# STM32F7.net
KiCad netlist of a schematic drawn in Altium Designer
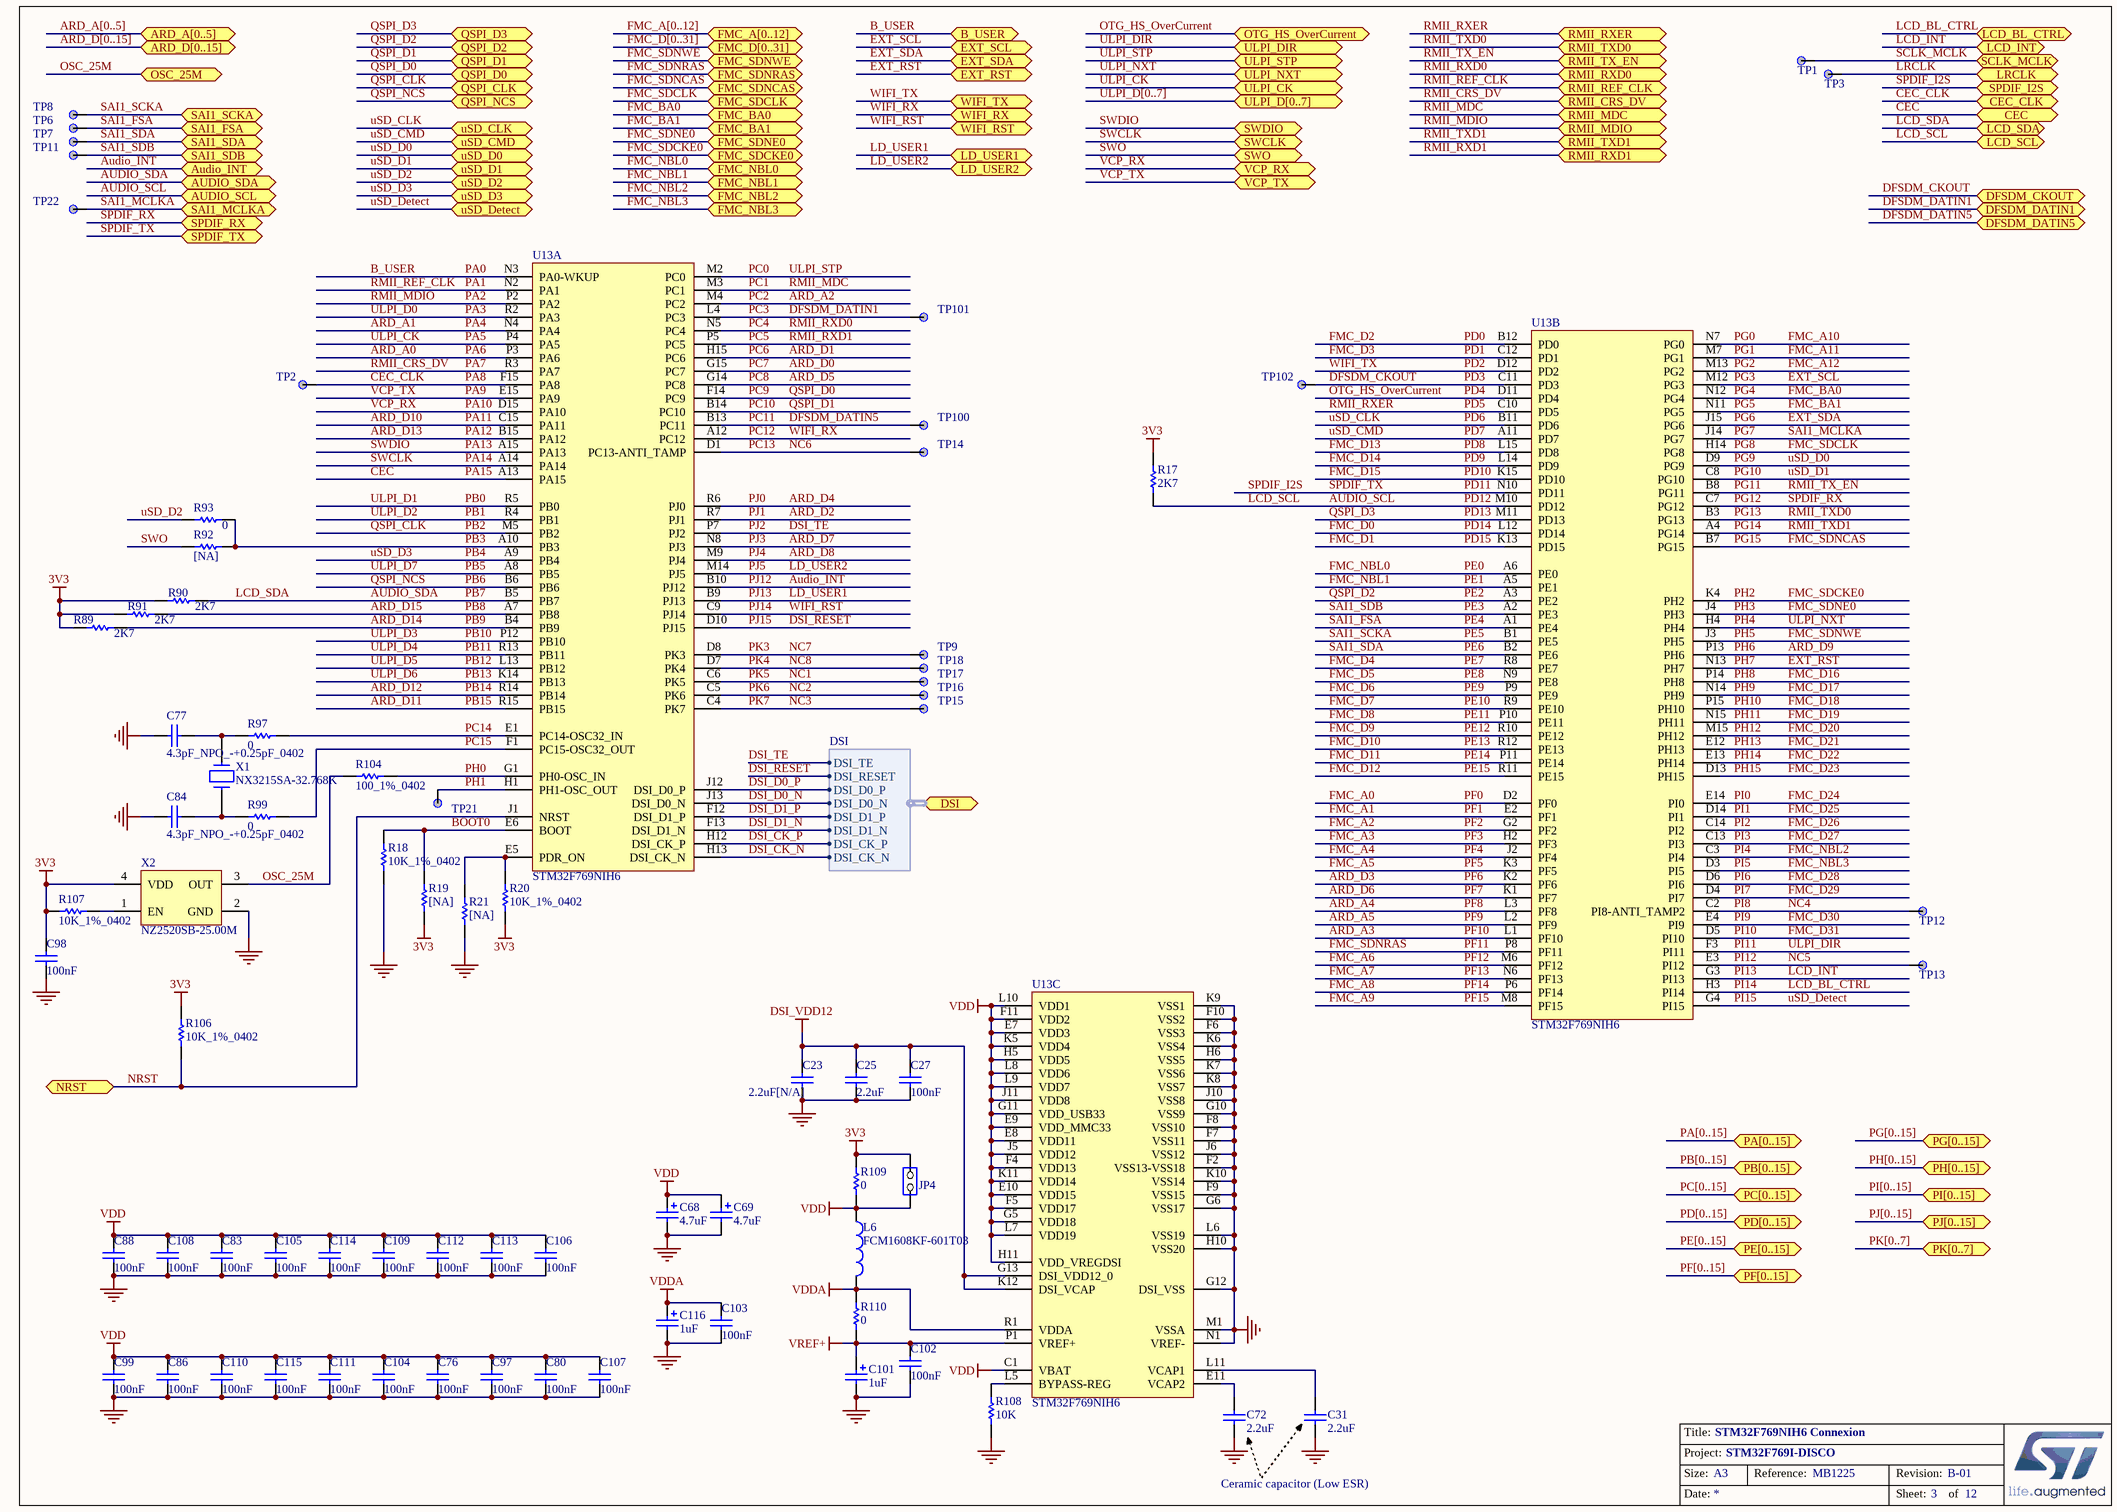
[diagram p0: STM32F7.SchDoc]

(export (version "E")
  (design (tool "Eeschema 10.0.6"))
  (components
    (comp (ref "C23")
      (value "2.2uF[N/A]")
      (footprint "1206C")
      (description "Capacitor,2.2uF,16V, X7R,10%,1206,YAGEO")
      (libsource (lib "MCD_TOOLS_CAPACITOR") (part "Cap_2.2uF_X7R_10%_1206"))
    )
    (comp (ref "C25")
      (value "2.2uF")
      (footprint "0603C")
      (description "Capacitor,2.2uF,10V, X5R,10%,0603,YAGEO")
      (libsource (lib "MCD_TOOLS_CAPACITOR") (part "Cap_2.2uF_X5R_10%_0603"))
    )
    (comp (ref "C27")
      (value "100nF")
      (footprint "0402C")
      (description "Capacitor,100nF,16V,X7R,10%,0402,YAGEO")
      (libsource (lib "MCD_TOOLS_CAPACITOR") (part "Cap_100nF_X7R_10%_0402"))
    )
    (comp (ref "C31")
      (value "2.2uF")
      (footprint "1206C")
      (description "Capacitor,2.2uF,16V, X7R,10%,1206,YAGEO")
      (libsource (lib "MCD_TOOLS") (part "Cap_2.2uF_X7R_10%_1206"))
    )
    (comp (ref "C68")
      (value "4.7uF")
      (footprint "TAN-A")
      (description "Polarized Capacitor,4.7uF,16V,10%,typeA,AVX")
      (libsource (lib "MCD_TOOLS") (part "Cap_4.7uF_POL_10%_TANA"))
    )
    (comp (ref "C69")
      (value "4.7uF")
      (footprint "TAN-A")
      (description "Polarized Capacitor,4.7uF,16V,10%,typeA,AVX")
      (libsource (lib "MCD_TOOLS") (part "Cap_4.7uF_POL_10%_TANA"))
    )
    (comp (ref "C72")
      (value "2.2uF")
      (footprint "1206C")
      (description "Capacitor,2.2uF,16V, X7R,10%,1206,YAGEO")
      (libsource (lib "MCD_TOOLS") (part "Cap_2.2uF_X7R_10%_1206"))
    )
    (comp (ref "C76")
      (value "100nF")
      (footprint "0402C")
      (description "Capacitor,100nF,16V,X7R,10%,0402,YAGEO")
      (libsource (lib "MCD_TOOLS") (part "Cap_100nF_X7R_10%_0402"))
    )
    (comp (ref "C77")
      (value "4.3pF_NPO_-+0.25pF_0402")
      (footprint "0402C")
      (description "Capacitor, 4.3pF, 16V, NPO, -+0.25pF, 0402, KEMET")
      (libsource (lib "MCD_TOOLS_CAPACITOR") (part "Cap_4.3pF_NPO_-+0.25pF_0402"))
    )
    (comp (ref "C80")
      (value "100nF")
      (footprint "0402C")
      (description "Capacitor,100nF,16V,X7R,10%,0402,YAGEO")
      (libsource (lib "MCD_TOOLS") (part "Cap_100nF_X7R_10%_0402"))
    )
    (comp (ref "C83")
      (value "100nF")
      (footprint "0402C")
      (description "Capacitor,100nF,16V,X7R,10%,0402,YAGEO")
      (libsource (lib "MCD_TOOLS") (part "Cap_100nF_X7R_10%_0402"))
    )
    (comp (ref "C84")
      (value "4.3pF_NPO_-+0.25pF_0402")
      (footprint "0402C")
      (description "Capacitor, 4.3pF, 16V, NPO, -+0.25pF, 0402, KEMET")
      (libsource (lib "MCD_TOOLS_CAPACITOR") (part "Cap_4.3pF_NPO_-+0.25pF_0402"))
    )
    (comp (ref "C86")
      (value "100nF")
      (footprint "0402C")
      (description "Capacitor,100nF,16V,X7R,10%,0402,YAGEO")
      (libsource (lib "MCD_TOOLS") (part "Cap_100nF_X7R_10%_0402"))
    )
    (comp (ref "C88")
      (value "100nF")
      (footprint "0402C")
      (description "Capacitor,100nF,16V,X7R,10%,0402,YAGEO")
      (libsource (lib "MCD_TOOLS") (part "Cap_100nF_X7R_10%_0402"))
    )
    (comp (ref "C97")
      (value "100nF")
      (footprint "0402C")
      (description "Capacitor,100nF,16V,X7R,10%,0402,YAGEO")
      (libsource (lib "MCD_TOOLS") (part "Cap_100nF_X7R_10%_0402"))
    )
    (comp (ref "C98")
      (value "100nF")
      (footprint "0402C")
      (description "Capacitor,100nF,16V,X7R,10%,0402,YAGEO")
      (libsource (lib "MCD_TOOLS") (part "Cap_100nF_X7R_10%_0402"))
    )
    (comp (ref "C99")
      (value "100nF")
      (footprint "0402C")
      (description "Capacitor,100nF,16V,X7R,10%,0402,YAGEO")
      (libsource (lib "MCD_TOOLS") (part "Cap_100nF_X7R_10%_0402"))
    )
    (comp (ref "C101")
      (value "1uF")
      (footprint "TAN-A")
      (description "Polarized Capacitor,1uF,16V,10%,typeA,AVX")
      (libsource (lib "MCD_TOOLS") (part "Cap_1uF_POL_10%_TANA"))
    )
    (comp (ref "C102")
      (value "100nF")
      (footprint "0402C")
      (description "Capacitor,100nF,16V,X7R,10%,0402,YAGEO")
      (libsource (lib "MCD_TOOLS") (part "Cap_100nF_X7R_10%_0402"))
    )
    (comp (ref "C103")
      (value "100nF")
      (footprint "0402C")
      (description "Capacitor,100nF,16V,X7R,10%,0402,YAGEO")
      (libsource (lib "MCD_TOOLS") (part "Cap_100nF_X7R_10%_0402"))
    )
    (comp (ref "C104")
      (value "100nF")
      (footprint "0402C")
      (description "Capacitor,100nF,16V,X7R,10%,0402,YAGEO")
      (libsource (lib "MCD_TOOLS") (part "Cap_100nF_X7R_10%_0402"))
    )
    (comp (ref "C105")
      (value "100nF")
      (footprint "0402C")
      (description "Capacitor,100nF,16V,X7R,10%,0402,YAGEO")
      (libsource (lib "MCD_TOOLS") (part "Cap_100nF_X7R_10%_0402"))
    )
    (comp (ref "C106")
      (value "100nF")
      (footprint "0402C")
      (description "Capacitor,100nF,16V,X7R,10%,0402,YAGEO")
      (libsource (lib "MCD_TOOLS") (part "Cap_100nF_X7R_10%_0402"))
    )
    (comp (ref "C107")
      (value "100nF")
      (footprint "0402C")
      (description "Capacitor,100nF,16V,X7R,10%,0402,YAGEO")
      (libsource (lib "MCD_TOOLS") (part "Cap_100nF_X7R_10%_0402"))
    )
    (comp (ref "C108")
      (value "100nF")
      (footprint "0402C")
      (description "Capacitor,100nF,16V,X7R,10%,0402,YAGEO")
      (libsource (lib "MCD_TOOLS") (part "Cap_100nF_X7R_10%_0402"))
    )
    (comp (ref "C109")
      (value "100nF")
      (footprint "0402C")
      (description "Capacitor,100nF,16V,X7R,10%,0402,YAGEO")
      (libsource (lib "MCD_TOOLS") (part "Cap_100nF_X7R_10%_0402"))
    )
    (comp (ref "C110")
      (value "100nF")
      (footprint "0402C")
      (description "Capacitor,100nF,16V,X7R,10%,0402,YAGEO")
      (libsource (lib "MCD_TOOLS") (part "Cap_100nF_X7R_10%_0402"))
    )
    (comp (ref "C111")
      (value "100nF")
      (footprint "0402C")
      (description "Capacitor,100nF,16V,X7R,10%,0402,YAGEO")
      (libsource (lib "MCD_TOOLS") (part "Cap_100nF_X7R_10%_0402"))
    )
    (comp (ref "C112")
      (value "100nF")
      (footprint "0402C")
      (description "Capacitor,100nF,16V,X7R,10%,0402,YAGEO")
      (libsource (lib "MCD_TOOLS") (part "Cap_100nF_X7R_10%_0402"))
    )
    (comp (ref "C113")
      (value "100nF")
      (footprint "0402C")
      (description "Capacitor,100nF,16V,X7R,10%,0402,YAGEO")
      (libsource (lib "MCD_TOOLS") (part "Cap_100nF_X7R_10%_0402"))
    )
    (comp (ref "C114")
      (value "100nF")
      (footprint "0402C")
      (description "Capacitor,100nF,16V,X7R,10%,0402,YAGEO")
      (libsource (lib "MCD_TOOLS") (part "Cap_100nF_X7R_10%_0402"))
    )
    (comp (ref "C115")
      (value "100nF")
      (footprint "0402C")
      (description "Capacitor,100nF,16V,X7R,10%,0402,YAGEO")
      (libsource (lib "MCD_TOOLS") (part "Cap_100nF_X7R_10%_0402"))
    )
    (comp (ref "C116")
      (value "1uF")
      (footprint "TAN-A")
      (description "Polarized Capacitor,1uF,16V,10%,typeA,AVX")
      (libsource (lib "MCD_TOOLS") (part "Cap_1uF_POL_10%_TANA"))
    )
    (comp (ref "JP4") (value "JP2") (footprint "SIP2") (libsource (lib "MCD_TOOLS_CONNECTOR") (part "JP2")))
    (comp (ref "L6")
      (value "FCM1608KF-601T03")
      (footprint "0603L")
      (description "Bead,600R,350mA,0603,FCM1608KF-601T03,Tai-tech")
      (libsource (lib "MCD_TOOLS") (part "BEAD_600R_350MA_0603"))
    )
    (comp (ref "R17")
      (value "2K7")
      (footprint "0402R")
      (description "Resistor,2K7,0402,1%,YAGEO")
      (libsource (lib "MCD_TOOLS") (part "Res_2K7_1%_0402"))
    )
    (comp (ref "R18")
      (value "10K_1%_0402")
      (footprint "0402R")
      (description "Resistor,10K,0402,1%,YAGEO")
      (libsource (lib "MCD_TOOLS") (part "Res_10K_1%_0402"))
    )
    (comp (ref "R19")
      (value "[NA]")
      (footprint "0402R")
      (description "Resistor,[NA],0402")
      (libsource (lib "MCD_TOOLS") (part "Res_NA_0402"))
    )
    (comp (ref "R20")
      (value "10K_1%_0402")
      (footprint "0402R")
      (description "Resistor,10K,0402,1%,YAGEO")
      (libsource (lib "MCD_TOOLS") (part "Res_10K_1%_0402"))
    )
    (comp (ref "R21")
      (value "[NA]")
      (footprint "0402R")
      (description "Resistor,[NA],0402")
      (libsource (lib "MCD_TOOLS") (part "Res_NA_0402"))
    )
    (comp (ref "R89")
      (value "2K7")
      (footprint "0402R")
      (description "Resistor,2K7,0402,1%,YAGEO")
      (libsource (lib "MCD_TOOLS") (part "Res_2K7_1%_0402"))
    )
    (comp (ref "R90")
      (value "2K7")
      (footprint "0402R")
      (description "Resistor,2K7,0402,1%,YAGEO")
      (libsource (lib "MCD_TOOLS") (part "Res_2K7_1%_0402"))
    )
    (comp (ref "R91")
      (value "2K7")
      (footprint "0402R")
      (description "Resistor,2K7,0402,1%,YAGEO")
      (libsource (lib "MCD_TOOLS") (part "Res_2K7_1%_0402"))
    )
    (comp (ref "R92")
      (value "[NA]")
      (footprint "0402R")
      (description "Resistor,[NA],0402")
      (libsource (lib "MCD_TOOLS_RESISTOR") (part "Res_NA_0402"))
    )
    (comp (ref "R93")
      (value "0")
      (footprint "0402R")
      (description "Resistor,0,0402,5%,YAGEO")
      (libsource (lib "MCD_TOOLS_RESISTOR") (part "Res_0_5%_0402"))
    )
    (comp (ref "R97")
      (value "0")
      (footprint "0402R")
      (description "Resistor,0,0402,5%,YAGEO")
      (libsource (lib "MCD_TOOLS") (part "Res_0_5%_0402"))
    )
    (comp (ref "R99")
      (value "0")
      (footprint "0402R")
      (description "Resistor,0,0402,5%,YAGEO")
      (libsource (lib "MCD_TOOLS") (part "Res_0_5%_0402"))
    )
    (comp (ref "R104")
      (value "100_1%_0402")
      (footprint "0402R")
      (description "Resistor,100,0402,1%,YAGEO")
      (libsource (lib "MCD_TOOLS") (part "Res_100_1%_0402"))
    )
    (comp (ref "R106")
      (value "10K_1%_0402")
      (footprint "0402R")
      (description "Resistor,10K,0402,1%,YAGEO")
      (libsource (lib "MCD_TOOLS") (part "Res_10K_1%_0402"))
    )
    (comp (ref "R107")
      (value "10K_1%_0402")
      (footprint "0402R")
      (description "Resistor,10K,0402,1%,YAGEO")
      (libsource (lib "MCD_TOOLS") (part "Res_10K_1%_0402"))
    )
    (comp (ref "R108")
      (value "10K")
      (footprint "0402R")
      (description "Resistor,10K,0402,1%,YAGEO")
      (libsource (lib "MCD_TOOLS") (part "Res_10K_1%_0402"))
    )
    (comp (ref "R109")
      (value "0")
      (footprint "0603R-GS")
      (description "Resistor,0,0603,5%,YAGEO")
      (libsource (lib "MCD_TOOLS") (part "Res_0_5%_0603"))
    )
    (comp (ref "R110")
      (value "0")
      (footprint "0603R-GS")
      (description "Resistor,0,0603,5%,YAGEO")
      (libsource (lib "MCD_TOOLS") (part "Res_0_5%_0603"))
    )
    (comp (ref "TP1")
      (value "TP")
      (footprint "TP_C40")
      (description "Test Point CMS")
      (libsource (lib "MCD_TOOLS_CONNECTOR") (part "TP"))
    )
    (comp (ref "TP2")
      (value "TP")
      (footprint "TP_C40")
      (description "Test Point CMS")
      (libsource (lib "MCD_TOOLS_CONNECTOR") (part "TP"))
    )
    (comp (ref "TP3")
      (value "TP")
      (footprint "TP_C40")
      (description "Test Point CMS")
      (libsource (lib "MCD_TOOLS_CONNECTOR") (part "TP"))
    )
    (comp (ref "TP6")
      (value "TP")
      (footprint "TP_C40")
      (description "Test Point CMS")
      (libsource (lib "MCD_TOOLS_CONNECTOR") (part "TP"))
    )
    (comp (ref "TP7")
      (value "TP")
      (footprint "TP_C40")
      (description "Test Point CMS")
      (libsource (lib "MCD_TOOLS_CONNECTOR") (part "TP"))
    )
    (comp (ref "TP8")
      (value "TP")
      (footprint "TP_C40")
      (description "Test Point CMS")
      (libsource (lib "MCD_TOOLS_CONNECTOR") (part "TP"))
    )
    (comp (ref "TP9")
      (value "TP")
      (footprint "TP_C40")
      (description "Test Point CMS")
      (libsource (lib "MCD_TOOLS_CONNECTOR") (part "TP"))
    )
    (comp (ref "TP11")
      (value "TP")
      (footprint "TP_C40")
      (description "Test Point CMS")
      (libsource (lib "MCD_TOOLS_CONNECTOR") (part "TP"))
    )
    (comp (ref "TP12")
      (value "TP")
      (footprint "TP_C40")
      (description "Test Point CMS")
      (libsource (lib "MCD_TOOLS_CONNECTOR") (part "TP"))
    )
    (comp (ref "TP13")
      (value "TP")
      (footprint "TP_C40")
      (description "Test Point CMS")
      (libsource (lib "MCD_TOOLS_CONNECTOR") (part "TP"))
    )
    (comp (ref "TP14")
      (value "TP")
      (footprint "TP_C40")
      (description "Test Point CMS")
      (libsource (lib "MCD_TOOLS_CONNECTOR") (part "TP"))
    )
    (comp (ref "TP15")
      (value "TP")
      (footprint "TP_C40")
      (description "Test Point CMS")
      (libsource (lib "MCD_TOOLS_CONNECTOR") (part "TP"))
    )
    (comp (ref "TP16")
      (value "TP")
      (footprint "TP_C40")
      (description "Test Point CMS")
      (libsource (lib "MCD_TOOLS_CONNECTOR") (part "TP"))
    )
    (comp (ref "TP17")
      (value "TP")
      (footprint "TP_C40")
      (description "Test Point CMS")
      (libsource (lib "MCD_TOOLS_CONNECTOR") (part "TP"))
    )
    (comp (ref "TP18")
      (value "TP")
      (footprint "TP_C40")
      (description "Test Point CMS")
      (libsource (lib "MCD_TOOLS_CONNECTOR") (part "TP"))
    )
    (comp (ref "TP21")
      (value "TP")
      (footprint "TP_C40")
      (description "Test Point CMS")
      (libsource (lib "MCD_TOOLS_CONNECTOR") (part "TP"))
    )
    (comp (ref "TP22")
      (value "TP")
      (footprint "TP_C40")
      (description "Test Point CMS")
      (libsource (lib "MCD_TOOLS_CONNECTOR") (part "TP"))
    )
    (comp (ref "TP100")
      (value "TP")
      (footprint "TP_C40")
      (description "Test Point CMS")
      (libsource (lib "MCD_TOOLS_CONNECTOR") (part "TP"))
    )
    (comp (ref "TP101")
      (value "TP")
      (footprint "TP_C40")
      (description "Test Point CMS")
      (libsource (lib "MCD_TOOLS_CONNECTOR") (part "TP"))
    )
    (comp (ref "TP102")
      (value "TP")
      (footprint "TP_C40")
      (description "Test Point CMS")
      (libsource (lib "MCD_TOOLS_CONNECTOR") (part "TP"))
    )
    (comp (ref "U13")
      (value "STM32F769NIH6")
      (footprint "BGA216_0R8_13X13")
      (description "STM32F769NIH6 (STM32F7 Big Birdie) TBGA216")
      (libsource (lib "MCD_TOOLS_MCU") (part "STM32F769NIH6U"))
    )
    (comp (ref "X1")
      (value "NX3215SA-32.768K")
      (footprint "XTAL_2SM_3R2X1R5")
      (description "Crystal 32.768kHz, 6pF, -+20PPM, NDK only for ST, Type NX3215SA,  NDK Spec EXS00A-MU00525")
      (libsource (lib "MCD_TOOLS") (part "XTAL_32K_NX3215SA"))
    )
    (comp (ref "X2")
      (value "NZ2520SB-25.00M")
      (footprint "OSC_4SM_2R5X2")
      (description "Oscillator 25.00Mhz, -+50PPM, 3.3V, Temp -55 to +125°C")
      (libsource (lib "MCD_TOOLS_MISCELLANEOUS") (part "OSC_25M_NZ2520SB"))
    )
  )
  (nets
    (net (code "11") (name "/ARD_A0") (class "Default")
      (node (ref "U13") (pin "P3") (pinfunction "PA6_P3") (pintype "passive"))
    )
    (net (code "12") (name "/ARD_A1") (class "Default")
      (node (ref "U13") (pin "N4") (pinfunction "PA4_N4") (pintype "passive"))
    )
    (net (code "13") (name "/ARD_A2") (class "Default")
      (node (ref "U13") (pin "M4") (pinfunction "PC2_M4") (pintype "passive"))
    )
    (net (code "14") (name "/ARD_A3") (class "Default")
      (node (ref "U13") (pin "L1") (pinfunction "PF10_L1") (pintype "passive"))
    )
    (net (code "15") (name "/ARD_A4") (class "Default")
      (node (ref "U13") (pin "L3") (pinfunction "PF8_L3") (pintype "passive"))
    )
    (net (code "16") (name "/ARD_A5") (class "Default")
      (node (ref "U13") (pin "L2") (pinfunction "PF9_L2") (pintype "passive"))
    )
    (net (code "18") (name "/ARD_D0") (class "Default")
      (node (ref "U13") (pin "G15") (pinfunction "PC7_G15") (pintype "passive"))
    )
    (net (code "19") (name "/ARD_D1") (class "Default")
      (node (ref "U13") (pin "H15") (pinfunction "PC6_H15") (pintype "passive"))
    )
    (net (code "20") (name "/ARD_D2") (class "Default")
      (node (ref "U13") (pin "R7") (pinfunction "PJ1_R7") (pintype "passive"))
    )
    (net (code "21") (name "/ARD_D3") (class "Default")
      (node (ref "U13") (pin "K2") (pinfunction "PF6_K2") (pintype "passive"))
    )
    (net (code "22") (name "/ARD_D4") (class "Default")
      (node (ref "U13") (pin "R6") (pinfunction "PJ0_R6") (pintype "passive"))
    )
    (net (code "23") (name "/ARD_D5") (class "Default")
      (node (ref "U13") (pin "G14") (pinfunction "PC8_G14") (pintype "passive"))
    )
    (net (code "24") (name "/ARD_D6") (class "Default")
      (node (ref "U13") (pin "K1") (pinfunction "PF7_K1") (pintype "passive"))
    )
    (net (code "25") (name "/ARD_D7") (class "Default")
      (node (ref "U13") (pin "N8") (pinfunction "PJ3_N8") (pintype "passive"))
    )
    (net (code "26") (name "/ARD_D8") (class "Default")
      (node (ref "U13") (pin "M9") (pinfunction "PJ4_M9") (pintype "passive"))
    )
    (net (code "27") (name "/ARD_D9") (class "Default")
      (node (ref "U13") (pin "P13") (pinfunction "PH6_P13") (pintype "passive"))
    )
    (net (code "28") (name "/ARD_D10") (class "Default")
      (node (ref "U13") (pin "C15") (pinfunction "PA11_C15") (pintype "passive"))
    )
    (net (code "29") (name "/ARD_D11") (class "Default")
      (node (ref "U13") (pin "R15") (pinfunction "PB15_R15") (pintype "passive"))
    )
    (net (code "30") (name "/ARD_D12") (class "Default")
      (node (ref "U13") (pin "R14") (pinfunction "PB14_R14") (pintype "passive"))
    )
    (net (code "31") (name "/ARD_D13") (class "Default")
      (node (ref "U13") (pin "B15") (pinfunction "PA12_B15") (pintype "passive"))
    )
    (net (code "32") (name "/ARD_D14") (class "Default")
      (node (ref "R89") (pin "2") (pinfunction "2_2") (pintype "passive"))
      (node (ref "U13") (pin "B4") (pinfunction "PB9_B4") (pintype "passive"))
    )
    (net (code "33") (name "/ARD_D15") (class "Default")
      (node (ref "R91") (pin "2") (pinfunction "2_2") (pintype "passive"))
      (node (ref "U13") (pin "A7") (pinfunction "PB8_A7") (pintype "passive"))
    )
    (net (code "35") (name "/BOOT0") (class "Default")
      (node (ref "R18") (pin "2") (pinfunction "2_2") (pintype "passive"))
      (node (ref "R19") (pin "2") (pinfunction "2_2") (pintype "passive"))
      (node (ref "U13") (pin "E6") (pinfunction "BOOT_E6") (pintype "passive"))
    )
    (net (code "36") (name "/DSI_CK_N") (class "Default")
      (node (ref "U13") (pin "H13") (pinfunction "DSI_CK_N_H13") (pintype "passive"))
    )
    (net (code "37") (name "/DSI_CK_P") (class "Default")
      (node (ref "U13") (pin "H12") (pinfunction "DSI_CK_P_H12") (pintype "passive"))
    )
    (net (code "38") (name "/DSI_D0_N") (class "Default")
      (node (ref "U13") (pin "J13") (pinfunction "DSI_D0_N_J13") (pintype "passive"))
    )
    (net (code "39") (name "/DSI_D0_P") (class "Default")
      (node (ref "U13") (pin "J12") (pinfunction "DSI_D0_P_J12") (pintype "passive"))
    )
    (net (code "40") (name "/DSI_D1_N") (class "Default")
      (node (ref "U13") (pin "F13") (pinfunction "DSI_D1_N_F13") (pintype "passive"))
    )
    (net (code "41") (name "/DSI_D1_P") (class "Default")
      (node (ref "U13") (pin "F12") (pinfunction "DSI_D1_P_F12") (pintype "passive"))
    )
    (net (code "42") (name "/FMC_A0") (class "Default")
      (node (ref "U13") (pin "D2") (pinfunction "PF0_D2") (pintype "passive"))
    )
    (net (code "43") (name "/FMC_A1") (class "Default")
      (node (ref "U13") (pin "E2") (pinfunction "PF1_E2") (pintype "passive"))
    )
    (net (code "44") (name "/FMC_A2") (class "Default")
      (node (ref "U13") (pin "G2") (pinfunction "PF2_G2") (pintype "passive"))
    )
    (net (code "45") (name "/FMC_A3") (class "Default")
      (node (ref "U13") (pin "H2") (pinfunction "PF3_H2") (pintype "passive"))
    )
    (net (code "46") (name "/FMC_A4") (class "Default")
      (node (ref "U13") (pin "J2") (pinfunction "PF4_J2") (pintype "passive"))
    )
    (net (code "47") (name "/FMC_A5") (class "Default")
      (node (ref "U13") (pin "K3") (pinfunction "PF5_K3") (pintype "passive"))
    )
    (net (code "48") (name "/FMC_A6") (class "Default")
      (node (ref "U13") (pin "M6") (pinfunction "PF12_M6") (pintype "passive"))
    )
    (net (code "49") (name "/FMC_A7") (class "Default")
      (node (ref "U13") (pin "N6") (pinfunction "PF13_N6") (pintype "passive"))
    )
    (net (code "50") (name "/FMC_A8") (class "Default")
      (node (ref "U13") (pin "P6") (pinfunction "PF14_P6") (pintype "passive"))
    )
    (net (code "51") (name "/FMC_A9") (class "Default")
      (node (ref "U13") (pin "M8") (pinfunction "PF15_M8") (pintype "passive"))
    )
    (net (code "52") (name "/FMC_A10") (class "Default")
      (node (ref "U13") (pin "N7") (pinfunction "PG0_N7") (pintype "passive"))
    )
    (net (code "53") (name "/FMC_A11") (class "Default")
      (node (ref "U13") (pin "M7") (pinfunction "PG1_M7") (pintype "passive"))
    )
    (net (code "54") (name "/FMC_A12") (class "Default")
      (node (ref "U13") (pin "M13") (pinfunction "PG2_M13") (pintype "passive"))
    )
    (net (code "56") (name "/FMC_D0") (class "Default")
      (node (ref "U13") (pin "L12") (pinfunction "PD14_L12") (pintype "passive"))
    )
    (net (code "57") (name "/FMC_D1") (class "Default")
      (node (ref "U13") (pin "K13") (pinfunction "PD15_K13") (pintype "passive"))
    )
    (net (code "58") (name "/FMC_D2") (class "Default")
      (node (ref "U13") (pin "B12") (pinfunction "PD0_B12") (pintype "passive"))
    )
    (net (code "59") (name "/FMC_D3") (class "Default")
      (node (ref "U13") (pin "C12") (pinfunction "PD1_C12") (pintype "passive"))
    )
    (net (code "60") (name "/FMC_D4") (class "Default")
      (node (ref "U13") (pin "R8") (pinfunction "PE7_R8") (pintype "passive"))
    )
    (net (code "61") (name "/FMC_D5") (class "Default")
      (node (ref "U13") (pin "N9") (pinfunction "PE8_N9") (pintype "passive"))
    )
    (net (code "62") (name "/FMC_D6") (class "Default")
      (node (ref "U13") (pin "P9") (pinfunction "PE9_P9") (pintype "passive"))
    )
    (net (code "63") (name "/FMC_D7") (class "Default")
      (node (ref "U13") (pin "R9") (pinfunction "PE10_R9") (pintype "passive"))
    )
    (net (code "64") (name "/FMC_D8") (class "Default")
      (node (ref "U13") (pin "P10") (pinfunction "PE11_P10") (pintype "passive"))
    )
    (net (code "65") (name "/FMC_D9") (class "Default")
      (node (ref "U13") (pin "R10") (pinfunction "PE12_R10") (pintype "passive"))
    )
    (net (code "66") (name "/FMC_D10") (class "Default")
      (node (ref "U13") (pin "R12") (pinfunction "PE13_R12") (pintype "passive"))
    )
    (net (code "67") (name "/FMC_D11") (class "Default")
      (node (ref "U13") (pin "P11") (pinfunction "PE14_P11") (pintype "passive"))
    )
    (net (code "68") (name "/FMC_D12") (class "Default")
      (node (ref "U13") (pin "R11") (pinfunction "PE15_R11") (pintype "passive"))
    )
    (net (code "69") (name "/FMC_D13") (class "Default")
      (node (ref "U13") (pin "L15") (pinfunction "PD8_L15") (pintype "passive"))
    )
    (net (code "70") (name "/FMC_D14") (class "Default")
      (node (ref "U13") (pin "L14") (pinfunction "PD9_L14") (pintype "passive"))
    )
    (net (code "71") (name "/FMC_D15") (class "Default")
      (node (ref "U13") (pin "K15") (pinfunction "PD10_K15") (pintype "passive"))
    )
    (net (code "72") (name "/FMC_D16") (class "Default")
      (node (ref "U13") (pin "P14") (pinfunction "PH8_P14") (pintype "passive"))
    )
    (net (code "73") (name "/FMC_D17") (class "Default")
      (node (ref "U13") (pin "N14") (pinfunction "PH9_N14") (pintype "passive"))
    )
    (net (code "74") (name "/FMC_D18") (class "Default")
      (node (ref "U13") (pin "P15") (pinfunction "PH10_P15") (pintype "passive"))
    )
    (net (code "75") (name "/FMC_D19") (class "Default")
      (node (ref "U13") (pin "N15") (pinfunction "PH11_N15") (pintype "passive"))
    )
    (net (code "76") (name "/FMC_D20") (class "Default")
      (node (ref "U13") (pin "M15") (pinfunction "PH12_M15") (pintype "passive"))
    )
    (net (code "77") (name "/FMC_D21") (class "Default")
      (node (ref "U13") (pin "E12") (pinfunction "PH13_E12") (pintype "passive"))
    )
    (net (code "78") (name "/FMC_D22") (class "Default")
      (node (ref "U13") (pin "E13") (pinfunction "PH14_E13") (pintype "passive"))
    )
    (net (code "79") (name "/FMC_D23") (class "Default")
      (node (ref "U13") (pin "D13") (pinfunction "PH15_D13") (pintype "passive"))
    )
    (net (code "80") (name "/FMC_D24") (class "Default")
      (node (ref "U13") (pin "E14") (pinfunction "PI0_E14") (pintype "passive"))
    )
    (net (code "81") (name "/FMC_D25") (class "Default")
      (node (ref "U13") (pin "D14") (pinfunction "PI1_D14") (pintype "passive"))
    )
    (net (code "82") (name "/FMC_D26") (class "Default")
      (node (ref "U13") (pin "C14") (pinfunction "PI2_C14") (pintype "passive"))
    )
    (net (code "83") (name "/FMC_D27") (class "Default")
      (node (ref "U13") (pin "C13") (pinfunction "PI3_C13") (pintype "passive"))
    )
    (net (code "84") (name "/FMC_D28") (class "Default")
      (node (ref "U13") (pin "D6") (pinfunction "PI6_D6") (pintype "passive"))
    )
    (net (code "85") (name "/FMC_D29") (class "Default")
      (node (ref "U13") (pin "D4") (pinfunction "PI7_D4") (pintype "passive"))
    )
    (net (code "86") (name "/FMC_D30") (class "Default")
      (node (ref "U13") (pin "E4") (pinfunction "PI9_E4") (pintype "passive"))
    )
    (net (code "87") (name "/FMC_D31") (class "Default")
      (node (ref "U13") (pin "D5") (pinfunction "PI10_D5") (pintype "passive"))
    )
    (net (code "89") (name "/LRCLK") (class "Default")
      (node (ref "TP3") (pin "1") (pinfunction "1_1") (pintype "passive"))
    )
    (net (code "90") (name "/NRST") (class "Default")
      (node (ref "R106") (pin "1") (pinfunction "1_1") (pintype "passive"))
      (node (ref "U13") (pin "J1") (pinfunction "NRST_J1") (pintype "passive"))
    )
    (net (code "91") (name "/OSC_25M") (class "Default")
      (node (ref "R104") (pin "1") (pinfunction "1_1") (pintype "passive"))
      (node (ref "X2") (pin "3") (pinfunction "OUT_3") (pintype "passive"))
    )
    (net (code "92") (name "/PA0") (class "Default")
      (node (ref "U13") (pin "N3") (pinfunction "PA0-WKUP_N3") (pintype "passive"))
    )
    (net (code "93") (name "/PA1") (class "Default")
      (node (ref "U13") (pin "N2") (pinfunction "PA1_N2") (pintype "passive"))
    )
    (net (code "94") (name "/PA2") (class "Default")
      (node (ref "U13") (pin "P2") (pinfunction "PA2_P2") (pintype "passive"))
    )
    (net (code "95") (name "/PA5") (class "Default")
      (node (ref "U13") (pin "P4") (pinfunction "PA5_P4") (pintype "passive"))
    )
    (net (code "96") (name "/PA7") (class "Default")
      (node (ref "U13") (pin "R3") (pinfunction "PA7_R3") (pintype "passive"))
    )
    (net (code "97") (name "/PA8") (class "Default")
      (node (ref "TP2") (pin "1") (pinfunction "1_1") (pintype "passive"))
      (node (ref "U13") (pin "F15") (pinfunction "PA8_F15") (pintype "passive"))
    )
    (net (code "98") (name "/PA9") (class "Default")
      (node (ref "U13") (pin "E15") (pinfunction "PA9_E15") (pintype "passive"))
    )
    (net (code "99") (name "/PA10") (class "Default")
      (node (ref "U13") (pin "D15") (pinfunction "PA10_D15") (pintype "passive"))
    )
    (net (code "100") (name "/PA13") (class "Default")
      (node (ref "U13") (pin "A15") (pinfunction "PA13_A15") (pintype "passive"))
    )
    (net (code "101") (name "/PA14") (class "Default")
      (node (ref "U13") (pin "A14") (pinfunction "PA14_A14") (pintype "passive"))
    )
    (net (code "102") (name "/PA15") (class "Default")
      (node (ref "U13") (pin "A13") (pinfunction "PA15_A13") (pintype "passive"))
    )
    (net (code "104") (name "/PB2") (class "Default")
      (node (ref "U13") (pin "M5") (pinfunction "PB2_M5") (pintype "passive"))
    )
    (net (code "105") (name "/PB3") (class "Default")
      (node (ref "R92") (pin "2") (pinfunction "2_2") (pintype "passive"))
      (node (ref "R93") (pin "2") (pinfunction "2_2") (pintype "passive"))
      (node (ref "U13") (pin "A10") (pinfunction "PB3_A10") (pintype "passive"))
    )
    (net (code "106") (name "/PB4") (class "Default")
      (node (ref "U13") (pin "A9") (pinfunction "PB4_A9") (pintype "passive"))
    )
    (net (code "107") (name "/PB6") (class "Default")
      (node (ref "U13") (pin "B6") (pinfunction "PB6_B6") (pintype "passive"))
    )
    (net (code "108") (name "/PB7") (class "Default")
      (node (ref "R90") (pin "2") (pinfunction "2_2") (pintype "passive"))
      (node (ref "U13") (pin "B5") (pinfunction "PB7_B5") (pintype "passive"))
    )
    (net (code "110") (name "/PC0") (class "Default")
      (node (ref "U13") (pin "M2") (pinfunction "PC0_M2") (pintype "passive"))
    )
    (net (code "111") (name "/PC1") (class "Default")
      (node (ref "U13") (pin "M3") (pinfunction "PC1_M3") (pintype "passive"))
    )
    (net (code "112") (name "/PC3") (class "Default")
      (node (ref "TP101") (pin "1") (pinfunction "1_1") (pintype "passive"))
      (node (ref "U13") (pin "L4") (pinfunction "PC3_L4") (pintype "passive"))
    )
    (net (code "113") (name "/PC4") (class "Default")
      (node (ref "U13") (pin "N5") (pinfunction "PC4_N5") (pintype "passive"))
    )
    (net (code "114") (name "/PC5") (class "Default")
      (node (ref "U13") (pin "P5") (pinfunction "PC5_P5") (pintype "passive"))
    )
    (net (code "115") (name "/PC9") (class "Default")
      (node (ref "U13") (pin "F14") (pinfunction "PC9_F14") (pintype "passive"))
    )
    (net (code "116") (name "/PC10") (class "Default")
      (node (ref "U13") (pin "B14") (pinfunction "PC10_B14") (pintype "passive"))
    )
    (net (code "117") (name "/PC11") (class "Default")
      (node (ref "TP100") (pin "1") (pinfunction "1_1") (pintype "passive"))
      (node (ref "U13") (pin "B13") (pinfunction "PC11_B13") (pintype "passive"))
    )
    (net (code "118") (name "/PC12") (class "Default")
      (node (ref "U13") (pin "A12") (pinfunction "PC12_A12") (pintype "passive"))
    )
    (net (code "119") (name "/PC13") (class "Default")
      (node (ref "TP14") (pin "1") (pinfunction "1_1") (pintype "passive"))
      (node (ref "U13") (pin "D1") (pinfunction "PC13-ANTI_TAMP_D1") (pintype "passive"))
    )
    (net (code "120") (name "/PC14") (class "Default")
      (node (ref "R97") (pin "2") (pinfunction "2_2") (pintype "passive"))
      (node (ref "U13") (pin "E1") (pinfunction "PC14-OSC32_IN_E1") (pintype "passive"))
    )
    (net (code "121") (name "/PC15") (class "Default")
      (node (ref "R99") (pin "2") (pinfunction "2_2") (pintype "passive"))
      (node (ref "U13") (pin "F1") (pinfunction "PC15-OSC32_OUT_F1") (pintype "passive"))
    )
    (net (code "123") (name "/PD2") (class "Default")
      (node (ref "U13") (pin "D12") (pinfunction "PD2_D12") (pintype "passive"))
    )
    (net (code "124") (name "/PD3") (class "Default")
      (node (ref "TP102") (pin "1") (pinfunction "1_1") (pintype "passive"))
      (node (ref "U13") (pin "C11") (pinfunction "PD3_C11") (pintype "passive"))
    )
    (net (code "125") (name "/PD4") (class "Default")
      (node (ref "U13") (pin "D11") (pinfunction "PD4_D11") (pintype "passive"))
    )
    (net (code "126") (name "/PD5") (class "Default")
      (node (ref "U13") (pin "C10") (pinfunction "PD5_C10") (pintype "passive"))
    )
    (net (code "127") (name "/PD6") (class "Default")
      (node (ref "U13") (pin "B11") (pinfunction "PD6_B11") (pintype "passive"))
    )
    (net (code "128") (name "/PD7") (class "Default")
      (node (ref "U13") (pin "A11") (pinfunction "PD7_A11") (pintype "passive"))
    )
    (net (code "129") (name "/PD11") (class "Default")
      (node (ref "U13") (pin "N10") (pinfunction "PD11_N10") (pintype "passive"))
    )
    (net (code "130") (name "/PD12") (class "Default")
      (node (ref "R17") (pin "1") (pinfunction "1_1") (pintype "passive"))
      (node (ref "U13") (pin "M10") (pinfunction "PD12_M10") (pintype "passive"))
    )
    (net (code "131") (name "/PD13") (class "Default")
      (node (ref "U13") (pin "M11") (pinfunction "PD13_M11") (pintype "passive"))
    )
    (net (code "133") (name "/PE0") (class "Default")
      (node (ref "U13") (pin "A6") (pinfunction "PE0_A6") (pintype "passive"))
    )
    (net (code "134") (name "/PE1") (class "Default")
      (node (ref "U13") (pin "A5") (pinfunction "PE1_A5") (pintype "passive"))
    )
    (net (code "135") (name "/PE2") (class "Default")
      (node (ref "U13") (pin "A3") (pinfunction "PE2_A3") (pintype "passive"))
    )
    (net (code "136") (name "/PE3") (class "Default")
      (node (ref "TP11") (pin "1") (pinfunction "1_1") (pintype "passive"))
      (node (ref "U13") (pin "A2") (pinfunction "PE3_A2") (pintype "passive"))
    )
    (net (code "137") (name "/PE4") (class "Default")
      (node (ref "TP6") (pin "1") (pinfunction "1_1") (pintype "passive"))
      (node (ref "U13") (pin "A1") (pinfunction "PE4_A1") (pintype "passive"))
    )
    (net (code "138") (name "/PE5") (class "Default")
      (node (ref "TP8") (pin "1") (pinfunction "1_1") (pintype "passive"))
      (node (ref "U13") (pin "B1") (pinfunction "PE5_B1") (pintype "passive"))
    )
    (net (code "139") (name "/PE6") (class "Default")
      (node (ref "TP7") (pin "1") (pinfunction "1_1") (pintype "passive"))
      (node (ref "U13") (pin "B2") (pinfunction "PE6_B2") (pintype "passive"))
    )
    (net (code "141") (name "/PF11") (class "Default")
      (node (ref "U13") (pin "P8") (pinfunction "PF11_P8") (pintype "passive"))
    )
    (net (code "143") (name "/PG3") (class "Default")
      (node (ref "U13") (pin "M12") (pinfunction "PG3_M12") (pintype "passive"))
    )
    (net (code "144") (name "/PG4") (class "Default")
      (node (ref "U13") (pin "N12") (pinfunction "PG4_N12") (pintype "passive"))
    )
    (net (code "145") (name "/PG5") (class "Default")
      (node (ref "U13") (pin "N11") (pinfunction "PG5_N11") (pintype "passive"))
    )
    (net (code "146") (name "/PG6") (class "Default")
      (node (ref "U13") (pin "J15") (pinfunction "PG6_J15") (pintype "passive"))
    )
    (net (code "147") (name "/PG7") (class "Default")
      (node (ref "TP22") (pin "1") (pinfunction "1_1") (pintype "passive"))
      (node (ref "U13") (pin "J14") (pinfunction "PG7_J14") (pintype "passive"))
    )
    (net (code "148") (name "/PG8") (class "Default")
      (node (ref "U13") (pin "H14") (pinfunction "PG8_H14") (pintype "passive"))
    )
    (net (code "149") (name "/PG9") (class "Default")
      (node (ref "U13") (pin "D9") (pinfunction "PG9_D9") (pintype "passive"))
    )
    (net (code "150") (name "/PG10") (class "Default")
      (node (ref "U13") (pin "C8") (pinfunction "PG10_C8") (pintype "passive"))
    )
    (net (code "151") (name "/PG11") (class "Default")
      (node (ref "U13") (pin "B8") (pinfunction "PG11_B8") (pintype "passive"))
    )
    (net (code "152") (name "/PG12") (class "Default")
      (node (ref "U13") (pin "C7") (pinfunction "PG12_C7") (pintype "passive"))
    )
    (net (code "153") (name "/PG13") (class "Default")
      (node (ref "U13") (pin "B3") (pinfunction "PG13_B3") (pintype "passive"))
    )
    (net (code "154") (name "/PG14") (class "Default")
      (node (ref "U13") (pin "A4") (pinfunction "PG14_A4") (pintype "passive"))
    )
    (net (code "155") (name "/PG15") (class "Default")
      (node (ref "U13") (pin "B7") (pinfunction "PG15_B7") (pintype "passive"))
    )
    (net (code "157") (name "/PH0") (class "Default")
      (node (ref "R104") (pin "2") (pinfunction "2_2") (pintype "passive"))
      (node (ref "U13") (pin "G1") (pinfunction "PH0-OSC_IN_G1") (pintype "passive"))
    )
    (net (code "158") (name "/PH1") (class "Default")
      (node (ref "TP21") (pin "1") (pinfunction "1_1") (pintype "passive"))
      (node (ref "U13") (pin "H1") (pinfunction "PH1-OSC_OUT_H1") (pintype "passive"))
    )
    (net (code "159") (name "/PH2") (class "Default")
      (node (ref "U13") (pin "K4") (pinfunction "PH2_K4") (pintype "passive"))
    )
    (net (code "160") (name "/PH3") (class "Default")
      (node (ref "U13") (pin "J4") (pinfunction "PH3_J4") (pintype "passive"))
    )
    (net (code "161") (name "/PH4") (class "Default")
      (node (ref "U13") (pin "H4") (pinfunction "PH4_H4") (pintype "passive"))
    )
    (net (code "162") (name "/PH5") (class "Default")
      (node (ref "U13") (pin "J3") (pinfunction "PH5_J3") (pintype "passive"))
    )
    (net (code "163") (name "/PH7") (class "Default")
      (node (ref "U13") (pin "N13") (pinfunction "PH7_N13") (pintype "passive"))
    )
    (net (code "165") (name "/PI4") (class "Default")
      (node (ref "U13") (pin "C3") (pinfunction "PI4_C3") (pintype "passive"))
    )
    (net (code "166") (name "/PI5") (class "Default")
      (node (ref "U13") (pin "D3") (pinfunction "PI5_D3") (pintype "passive"))
    )
    (net (code "167") (name "/PI8") (class "Default")
      (node (ref "TP12") (pin "1") (pinfunction "1_1") (pintype "passive"))
      (node (ref "U13") (pin "C2") (pinfunction "PI8-ANTI_TAMP2_C2") (pintype "passive"))
    )
    (net (code "168") (name "/PI11") (class "Default")
      (node (ref "U13") (pin "F3") (pinfunction "PI11_F3") (pintype "passive"))
    )
    (net (code "169") (name "/PI12") (class "Default")
      (node (ref "TP13") (pin "1") (pinfunction "1_1") (pintype "passive"))
      (node (ref "U13") (pin "E3") (pinfunction "PI12_E3") (pintype "passive"))
    )
    (net (code "170") (name "/PI13") (class "Default")
      (node (ref "U13") (pin "G3") (pinfunction "PI13_G3") (pintype "passive"))
    )
    (net (code "171") (name "/PI14") (class "Default")
      (node (ref "U13") (pin "H3") (pinfunction "PI14_H3") (pintype "passive"))
    )
    (net (code "172") (name "/PI15") (class "Default")
      (node (ref "U13") (pin "G4") (pinfunction "PI15_G4") (pintype "passive"))
    )
    (net (code "174") (name "/PJ2") (class "Default")
      (node (ref "U13") (pin "P7") (pinfunction "PJ2_P7") (pintype "passive"))
    )
    (net (code "175") (name "/PJ5") (class "Default")
      (node (ref "U13") (pin "M14") (pinfunction "PJ5_M14") (pintype "passive"))
    )
    (net (code "176") (name "/PJ12") (class "Default")
      (node (ref "U13") (pin "B10") (pinfunction "PJ12_B10") (pintype "passive"))
    )
    (net (code "177") (name "/PJ13") (class "Default")
      (node (ref "U13") (pin "B9") (pinfunction "PJ13_B9") (pintype "passive"))
    )
    (net (code "178") (name "/PJ14") (class "Default")
      (node (ref "U13") (pin "C9") (pinfunction "PJ14_C9") (pintype "passive"))
    )
    (net (code "179") (name "/PJ15") (class "Default")
      (node (ref "U13") (pin "D10") (pinfunction "PJ15_D10") (pintype "passive"))
    )
    (net (code "181") (name "/PK3") (class "Default")
      (node (ref "TP9") (pin "1") (pinfunction "1_1") (pintype "passive"))
      (node (ref "U13") (pin "D8") (pinfunction "PK3_D8") (pintype "passive"))
    )
    (net (code "182") (name "/PK4") (class "Default")
      (node (ref "TP18") (pin "1") (pinfunction "1_1") (pintype "passive"))
      (node (ref "U13") (pin "D7") (pinfunction "PK4_D7") (pintype "passive"))
    )
    (net (code "183") (name "/PK5") (class "Default")
      (node (ref "TP17") (pin "1") (pinfunction "1_1") (pintype "passive"))
      (node (ref "U13") (pin "C6") (pinfunction "PK5_C6") (pintype "passive"))
    )
    (net (code "184") (name "/PK6") (class "Default")
      (node (ref "TP16") (pin "1") (pinfunction "1_1") (pintype "passive"))
      (node (ref "U13") (pin "C5") (pinfunction "PK6_C5") (pintype "passive"))
    )
    (net (code "185") (name "/PK7") (class "Default")
      (node (ref "TP15") (pin "1") (pinfunction "1_1") (pintype "passive"))
      (node (ref "U13") (pin "C4") (pinfunction "PK7_C4") (pintype "passive"))
    )
    (net (code "187") (name "/SCLK_MCLK") (class "Default")
      (node (ref "TP1") (pin "1") (pinfunction "1_1") (pintype "passive"))
    )
    (net (code "188") (name "/SWO") (class "Default")
      (node (ref "R92") (pin "1") (pinfunction "1_1") (pintype "passive"))
    )
    (net (code "189") (name "/ULPI_D0") (class "Default")
      (node (ref "U13") (pin "R2") (pinfunction "PA3_R2") (pintype "passive"))
    )
    (net (code "190") (name "/ULPI_D1") (class "Default")
      (node (ref "U13") (pin "R5") (pinfunction "PB0_R5") (pintype "passive"))
    )
    (net (code "191") (name "/ULPI_D2") (class "Default")
      (node (ref "U13") (pin "R4") (pinfunction "PB1_R4") (pintype "passive"))
    )
    (net (code "192") (name "/ULPI_D3") (class "Default")
      (node (ref "U13") (pin "P12") (pinfunction "PB10_P12") (pintype "passive"))
    )
    (net (code "193") (name "/ULPI_D4") (class "Default")
      (node (ref "U13") (pin "R13") (pinfunction "PB11_R13") (pintype "passive"))
    )
    (net (code "194") (name "/ULPI_D5") (class "Default")
      (node (ref "U13") (pin "L13") (pinfunction "PB12_L13") (pintype "passive"))
    )
    (net (code "195") (name "/ULPI_D6") (class "Default")
      (node (ref "U13") (pin "K14") (pinfunction "PB13_K14") (pintype "passive"))
    )
    (net (code "196") (name "/ULPI_D7") (class "Default")
      (node (ref "U13") (pin "A8") (pinfunction "PB5_A8") (pintype "passive"))
    )
    (net (code "198") (name "/uSD_D2") (class "Default")
      (node (ref "R93") (pin "1") (pinfunction "1_1") (pintype "passive"))
    )
    (net (code "200") (name "3V3") (class "Default")
      (node (ref "C98") (pin "2") (pinfunction "2_2") (pintype "passive"))
      (node (ref "JP4") (pin "2") (pinfunction "NO_2") (pintype "passive"))
      (node (ref "R106") (pin "2") (pinfunction "2_2") (pintype "passive"))
      (node (ref "R107") (pin "1") (pinfunction "1_1") (pintype "passive"))
      (node (ref "R109") (pin "2") (pinfunction "2_2") (pintype "passive"))
      (node (ref "R17") (pin "2") (pinfunction "2_2") (pintype "passive"))
      (node (ref "R19") (pin "1") (pinfunction "1_1") (pintype "passive"))
      (node (ref "R20") (pin "1") (pinfunction "1_1") (pintype "passive"))
      (node (ref "R89") (pin "1") (pinfunction "1_1") (pintype "passive"))
      (node (ref "R90") (pin "1") (pinfunction "1_1") (pintype "passive"))
      (node (ref "R91") (pin "1") (pinfunction "1_1") (pintype "passive"))
      (node (ref "X2") (pin "4") (pinfunction "VDD_4") (pintype "passive"))
    )
    (net (code "201") (name "DSI_VDD12") (class "Default")
      (node (ref "C23") (pin "2") (pinfunction "2_2") (pintype "passive"))
      (node (ref "C25") (pin "2") (pinfunction "2_2") (pintype "passive"))
      (node (ref "C27") (pin "2") (pinfunction "2_2") (pintype "passive"))
      (node (ref "U13") (pin "G13") (pinfunction "DSI_VDD12_0_G13") (pintype "power_in"))
      (node (ref "U13") (pin "K12") (pinfunction "DSI_VCAP_K12") (pintype "power_in"))
    )
    (net (code "202") (name "GND") (class "Default")
      (node (ref "C101") (pin "2") (pinfunction "2_2") (pintype "passive"))
      (node (ref "C102") (pin "1") (pinfunction "1_1") (pintype "passive"))
      (node (ref "C103") (pin "1") (pinfunction "1_1") (pintype "passive"))
      (node (ref "C104") (pin "1") (pinfunction "1_1") (pintype "passive"))
      (node (ref "C105") (pin "1") (pinfunction "1_1") (pintype "passive"))
      (node (ref "C106") (pin "1") (pinfunction "1_1") (pintype "passive"))
      (node (ref "C107") (pin "1") (pinfunction "1_1") (pintype "passive"))
      (node (ref "C108") (pin "1") (pinfunction "1_1") (pintype "passive"))
      (node (ref "C109") (pin "1") (pinfunction "1_1") (pintype "passive"))
      (node (ref "C110") (pin "1") (pinfunction "1_1") (pintype "passive"))
      (node (ref "C111") (pin "1") (pinfunction "1_1") (pintype "passive"))
      (node (ref "C112") (pin "1") (pinfunction "1_1") (pintype "passive"))
      (node (ref "C113") (pin "1") (pinfunction "1_1") (pintype "passive"))
      (node (ref "C114") (pin "1") (pinfunction "1_1") (pintype "passive"))
      (node (ref "C115") (pin "1") (pinfunction "1_1") (pintype "passive"))
      (node (ref "C116") (pin "2") (pinfunction "2_2") (pintype "passive"))
      (node (ref "C23") (pin "1") (pinfunction "1_1") (pintype "passive"))
      (node (ref "C25") (pin "1") (pinfunction "1_1") (pintype "passive"))
      (node (ref "C27") (pin "1") (pinfunction "1_1") (pintype "passive"))
      (node (ref "C31") (pin "1") (pinfunction "1_1") (pintype "passive"))
      (node (ref "C68") (pin "2") (pinfunction "2_2") (pintype "passive"))
      (node (ref "C69") (pin "2") (pinfunction "2_2") (pintype "passive"))
      (node (ref "C72") (pin "1") (pinfunction "1_1") (pintype "passive"))
      (node (ref "C76") (pin "1") (pinfunction "1_1") (pintype "passive"))
      (node (ref "C77") (pin "1") (pinfunction "1_1") (pintype "passive"))
      (node (ref "C80") (pin "1") (pinfunction "1_1") (pintype "passive"))
      (node (ref "C83") (pin "1") (pinfunction "1_1") (pintype "passive"))
      (node (ref "C84") (pin "1") (pinfunction "1_1") (pintype "passive"))
      (node (ref "C86") (pin "1") (pinfunction "1_1") (pintype "passive"))
      (node (ref "C88") (pin "1") (pinfunction "1_1") (pintype "passive"))
      (node (ref "C97") (pin "1") (pinfunction "1_1") (pintype "passive"))
      (node (ref "C98") (pin "1") (pinfunction "1_1") (pintype "passive"))
      (node (ref "C99") (pin "1") (pinfunction "1_1") (pintype "passive"))
      (node (ref "R108") (pin "1") (pinfunction "1_1") (pintype "passive"))
      (node (ref "R18") (pin "1") (pinfunction "1_1") (pintype "passive"))
      (node (ref "R21") (pin "1") (pinfunction "1_1") (pintype "passive"))
      (node (ref "U13") (pin "F10") (pinfunction "VSS2_F10") (pintype "passive"))
      (node (ref "U13") (pin "F2") (pinfunction "VSS13-VSS18_F2") (pintype "passive"))
      (node (ref "U13") (pin "F6") (pinfunction "VSS3_F6") (pintype "passive"))
      (node (ref "U13") (pin "F7") (pinfunction "VSS11_F7") (pintype "passive"))
      (node (ref "U13") (pin "F8") (pinfunction "VSS10_F8") (pintype "passive"))
      (node (ref "U13") (pin "F9") (pinfunction "VSS15_F9") (pintype "passive"))
      (node (ref "U13") (pin "G10") (pinfunction "VSS9_G10") (pintype "passive"))
      (node (ref "U13") (pin "G12") (pinfunction "DSI_VSS_G12") (pintype "power_in"))
      (node (ref "U13") (pin "G6") (pinfunction "VSS17_G6") (pintype "passive"))
      (node (ref "U13") (pin "H10") (pinfunction "VSS20_H10") (pintype "passive"))
      (node (ref "U13") (pin "H6") (pinfunction "VSS5_H6") (pintype "passive"))
      (node (ref "U13") (pin "J10") (pinfunction "VSS8_J10") (pintype "passive"))
      (node (ref "U13") (pin "J6") (pinfunction "VSS12_J6") (pintype "passive"))
      (node (ref "U13") (pin "K10") (pinfunction "VSS14_K10") (pintype "passive"))
      (node (ref "U13") (pin "K6") (pinfunction "VSS4_K6") (pintype "passive"))
      (node (ref "U13") (pin "K7") (pinfunction "VSS6_K7") (pintype "passive"))
      (node (ref "U13") (pin "K8") (pinfunction "VSS7_K8") (pintype "passive"))
      (node (ref "U13") (pin "K9") (pinfunction "VSS1_K9") (pintype "passive"))
      (node (ref "U13") (pin "L6") (pinfunction "VSS19_L6") (pintype "passive"))
      (node (ref "U13") (pin "M1") (pinfunction "VSSA_M1") (pintype "passive"))
      (node (ref "U13") (pin "N1") (pinfunction "VREF-_N1") (pintype "passive"))
      (node (ref "X2") (pin "2") (pinfunction "GND_2") (pintype "passive"))
    )
    (net (code "203") (name "Net-(C77-Pad2)") (class "Default")
      (node (ref "C77") (pin "2") (pinfunction "2_2") (pintype "passive"))
      (node (ref "R97") (pin "1") (pinfunction "1_1") (pintype "passive"))
      (node (ref "X1") (pin "1") (pinfunction "1_1") (pintype "passive"))
    )
    (net (code "204") (name "Net-(C84-Pad2)") (class "Default")
      (node (ref "C84") (pin "2") (pinfunction "2_2") (pintype "passive"))
      (node (ref "R99") (pin "1") (pinfunction "1_1") (pintype "passive"))
      (node (ref "X1") (pin "2") (pinfunction "2_2") (pintype "passive"))
    )
    (net (code "205") (name "Net-(U13A-PDR_ON)") (class "Default")
      (node (ref "R20") (pin "2") (pinfunction "2_2") (pintype "passive"))
      (node (ref "R21") (pin "2") (pinfunction "2_2") (pintype "passive"))
      (node (ref "U13") (pin "E5") (pinfunction "PDR_ON_E5") (pintype "passive"))
    )
    (net (code "206") (name "Net-(U13C-BYPASS-REG)") (class "Default")
      (node (ref "R108") (pin "2") (pinfunction "2_2") (pintype "passive"))
      (node (ref "U13") (pin "L5") (pinfunction "BYPASS-REG_L5") (pintype "passive"))
    )
    (net (code "207") (name "Net-(U13C-VCAP1)") (class "Default")
      (node (ref "C31") (pin "2") (pinfunction "2_2") (pintype "passive"))
      (node (ref "U13") (pin "L11") (pinfunction "VCAP1_L11") (pintype "passive"))
    )
    (net (code "208") (name "Net-(U13C-VCAP2)") (class "Default")
      (node (ref "C72") (pin "2") (pinfunction "2_2") (pintype "passive"))
      (node (ref "U13") (pin "E11") (pinfunction "VCAP2_E11") (pintype "passive"))
    )
    (net (code "209") (name "Net-(X2-EN)") (class "Default")
      (node (ref "R107") (pin "2") (pinfunction "2_2") (pintype "passive"))
      (node (ref "X2") (pin "1") (pinfunction "EN_1") (pintype "passive"))
    )
    (net (code "210") (name "VDD") (class "Default")
      (node (ref "C104") (pin "2") (pinfunction "2_2") (pintype "passive"))
      (node (ref "C105") (pin "2") (pinfunction "2_2") (pintype "passive"))
      (node (ref "C106") (pin "2") (pinfunction "2_2") (pintype "passive"))
      (node (ref "C107") (pin "2") (pinfunction "2_2") (pintype "passive"))
      (node (ref "C108") (pin "2") (pinfunction "2_2") (pintype "passive"))
      (node (ref "C109") (pin "2") (pinfunction "2_2") (pintype "passive"))
      (node (ref "C110") (pin "2") (pinfunction "2_2") (pintype "passive"))
      (node (ref "C111") (pin "2") (pinfunction "2_2") (pintype "passive"))
      (node (ref "C112") (pin "2") (pinfunction "2_2") (pintype "passive"))
      (node (ref "C113") (pin "2") (pinfunction "2_2") (pintype "passive"))
      (node (ref "C114") (pin "2") (pinfunction "2_2") (pintype "passive"))
      (node (ref "C115") (pin "2") (pinfunction "2_2") (pintype "passive"))
      (node (ref "C68") (pin "1") (pinfunction "1_1") (pintype "passive"))
      (node (ref "C69") (pin "1") (pinfunction "1_1") (pintype "passive"))
      (node (ref "C76") (pin "2") (pinfunction "2_2") (pintype "passive"))
      (node (ref "C80") (pin "2") (pinfunction "2_2") (pintype "passive"))
      (node (ref "C83") (pin "2") (pinfunction "2_2") (pintype "passive"))
      (node (ref "C86") (pin "2") (pinfunction "2_2") (pintype "passive"))
      (node (ref "C88") (pin "2") (pinfunction "2_2") (pintype "passive"))
      (node (ref "C97") (pin "2") (pinfunction "2_2") (pintype "passive"))
      (node (ref "C99") (pin "2") (pinfunction "2_2") (pintype "passive"))
      (node (ref "JP4") (pin "1") (pinfunction "COMMON_1") (pintype "passive"))
      (node (ref "L6") (pin "1") (pinfunction "1_1") (pintype "passive"))
      (node (ref "R109") (pin "1") (pinfunction "1_1") (pintype "passive"))
      (node (ref "U13") (pin "C1") (pinfunction "VBAT_C1") (pintype "passive"))
      (node (ref "U13") (pin "E10") (pinfunction "VDD15_E10") (pintype "passive"))
      (node (ref "U13") (pin "E7") (pinfunction "VDD3_E7") (pintype "passive"))
      (node (ref "U13") (pin "E8") (pinfunction "VDD11_E8") (pintype "passive"))
      (node (ref "U13") (pin "E9") (pinfunction "VDD_MMC33_E9") (pintype "passive"))
      (node (ref "U13") (pin "F11") (pinfunction "VDD2_F11") (pintype "passive"))
      (node (ref "U13") (pin "F4") (pinfunction "VDD13_F4") (pintype "passive"))
      (node (ref "U13") (pin "F5") (pinfunction "VDD17_F5") (pintype "passive"))
      (node (ref "U13") (pin "G11") (pinfunction "VDD_USB33_G11") (pintype "passive"))
      (node (ref "U13") (pin "G5") (pinfunction "VDD18_G5") (pintype "passive"))
      (node (ref "U13") (pin "H11") (pinfunction "VDD_VREGDSI_H11") (pintype "passive"))
      (node (ref "U13") (pin "H5") (pinfunction "VDD5_H5") (pintype "passive"))
      (node (ref "U13") (pin "J11") (pinfunction "VDD8_J11") (pintype "passive"))
      (node (ref "U13") (pin "J5") (pinfunction "VDD12_J5") (pintype "passive"))
      (node (ref "U13") (pin "K11") (pinfunction "VDD14_K11") (pintype "passive"))
      (node (ref "U13") (pin "K5") (pinfunction "VDD4_K5") (pintype "passive"))
      (node (ref "U13") (pin "L10") (pinfunction "VDD1_L10") (pintype "passive"))
      (node (ref "U13") (pin "L7") (pinfunction "VDD19_L7") (pintype "passive"))
      (node (ref "U13") (pin "L8") (pinfunction "VDD6_L8") (pintype "passive"))
      (node (ref "U13") (pin "L9") (pinfunction "VDD7_L9") (pintype "passive"))
    )
    (net (code "211") (name "VDDA") (class "Default")
      (node (ref "C103") (pin "2") (pinfunction "2_2") (pintype "passive"))
      (node (ref "C116") (pin "1") (pinfunction "1_1") (pintype "passive"))
      (node (ref "L6") (pin "2") (pinfunction "2_2") (pintype "passive"))
      (node (ref "R110") (pin "1") (pinfunction "1_1") (pintype "passive"))
      (node (ref "U13") (pin "R1") (pinfunction "VDDA_R1") (pintype "passive"))
    )
    (net (code "212") (name "VREF+") (class "Default")
      (node (ref "C101") (pin "1") (pinfunction "1_1") (pintype "passive"))
      (node (ref "C102") (pin "2") (pinfunction "2_2") (pintype "passive"))
      (node (ref "R110") (pin "2") (pinfunction "2_2") (pintype "passive"))
      (node (ref "U13") (pin "P1") (pinfunction "VREF+_P1") (pintype "passive"))
    )
  )
)
